# Sheet1_MEZ.net
KiCad netlist of a schematic drawn in Altium Designer
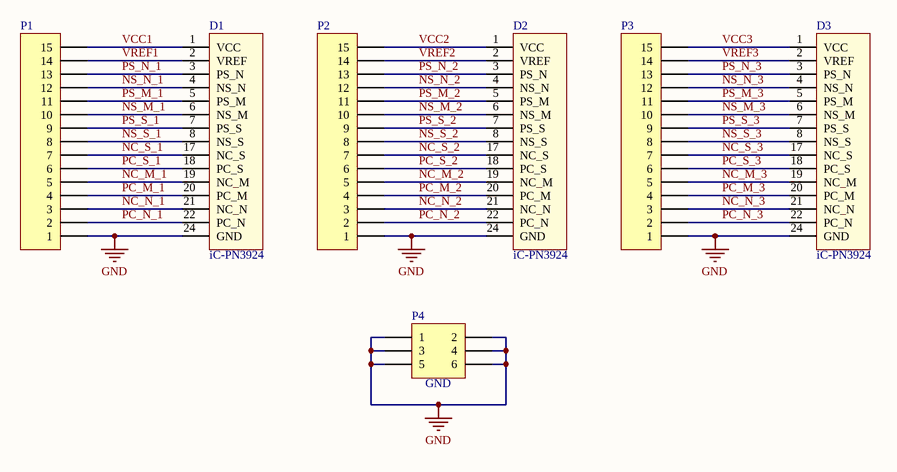
[diagram p0: Sheet1_MEZ.SchDoc]

(export (version "E")
  (design (tool "Eeschema 10.0.6"))
  (components
    (comp (ref "D1")
      (value "iC-PN3924")
      (footprint "iC-PN3924")
      (libsource (lib "Schlib") (part "iC-PN3924"))
    )
    (comp (ref "D2")
      (value "iC-PN3924")
      (footprint "iC-PN3924")
      (libsource (lib "Schlib") (part "iC-PN3924"))
    )
    (comp (ref "D3")
      (value "iC-PN3924")
      (footprint "iC-PN3924")
      (libsource (lib "Schlib") (part "iC-PN3924"))
    )
    (comp (ref "P1")
      (value "Header 15")
      (footprint "HDR1X15")
      (description "Header, 15-Pin")
      (fields (field (name "PUBLISHER") "Altium Limited"))
      (libsource (lib "Miscellaneous Connectors") (part "Header 15"))
    )
    (comp (ref "P2")
      (value "Header 15")
      (footprint "HDR1X15")
      (description "Header, 15-Pin")
      (fields (field (name "PUBLISHER") "Altium Limited"))
      (libsource (lib "Miscellaneous Connectors") (part "Header 15"))
    )
    (comp (ref "P3")
      (value "Header 15")
      (footprint "HDR1X15")
      (description "Header, 15-Pin")
      (fields (field (name "PUBLISHER") "Altium Limited"))
      (libsource (lib "Miscellaneous Connectors") (part "Header 15"))
    )
    (comp (ref "P4")
      (value "GND")
      (footprint "HDR2X3")
      (description "Header, 3-Pin, Dual row")
      (fields (field (name "PUBLISHER") "Altium Limited"))
      (libsource (lib "Miscellaneous Connectors") (part "Header 3X2"))
    )
  )
  (nets
    (net (code "1") (name "/NC_M_1") (class "Default")
      (node (ref "D1") (pin "19") (pinfunction "NC_M_19") (pintype "passive"))
      (node (ref "P1") (pin "5") (pinfunction "5_5") (pintype "passive"))
    )
    (net (code "2") (name "/NC_M_2") (class "Default")
      (node (ref "D2") (pin "19") (pinfunction "NC_M_19") (pintype "passive"))
      (node (ref "P2") (pin "5") (pinfunction "5_5") (pintype "passive"))
    )
    (net (code "3") (name "/NC_M_3") (class "Default")
      (node (ref "D3") (pin "19") (pinfunction "NC_M_19") (pintype "passive"))
      (node (ref "P3") (pin "5") (pinfunction "5_5") (pintype "passive"))
    )
    (net (code "4") (name "/NC_N_1") (class "Default")
      (node (ref "D1") (pin "21") (pinfunction "NC_N_21") (pintype "passive"))
      (node (ref "P1") (pin "3") (pinfunction "3_3") (pintype "passive"))
    )
    (net (code "5") (name "/NC_N_2") (class "Default")
      (node (ref "D2") (pin "21") (pinfunction "NC_N_21") (pintype "passive"))
      (node (ref "P2") (pin "3") (pinfunction "3_3") (pintype "passive"))
    )
    (net (code "6") (name "/NC_N_3") (class "Default")
      (node (ref "D3") (pin "21") (pinfunction "NC_N_21") (pintype "passive"))
      (node (ref "P3") (pin "3") (pinfunction "3_3") (pintype "passive"))
    )
    (net (code "7") (name "/NC_S_1") (class "Default")
      (node (ref "D1") (pin "17") (pinfunction "NC_S_17") (pintype "passive"))
      (node (ref "P1") (pin "7") (pinfunction "7_7") (pintype "passive"))
    )
    (net (code "8") (name "/NC_S_2") (class "Default")
      (node (ref "D2") (pin "17") (pinfunction "NC_S_17") (pintype "passive"))
      (node (ref "P2") (pin "7") (pinfunction "7_7") (pintype "passive"))
    )
    (net (code "9") (name "/NC_S_3") (class "Default")
      (node (ref "D3") (pin "17") (pinfunction "NC_S_17") (pintype "passive"))
      (node (ref "P3") (pin "7") (pinfunction "7_7") (pintype "passive"))
    )
    (net (code "10") (name "/NS_M_1") (class "Default")
      (node (ref "D1") (pin "6") (pinfunction "NS_M_6") (pintype "passive"))
      (node (ref "P1") (pin "10") (pinfunction "10_10") (pintype "passive"))
    )
    (net (code "11") (name "/NS_M_2") (class "Default")
      (node (ref "D2") (pin "6") (pinfunction "NS_M_6") (pintype "passive"))
      (node (ref "P2") (pin "10") (pinfunction "10_10") (pintype "passive"))
    )
    (net (code "12") (name "/NS_M_3") (class "Default")
      (node (ref "D3") (pin "6") (pinfunction "NS_M_6") (pintype "passive"))
      (node (ref "P3") (pin "10") (pinfunction "10_10") (pintype "passive"))
    )
    (net (code "13") (name "/NS_N_1") (class "Default")
      (node (ref "D1") (pin "4") (pinfunction "NS_N_4") (pintype "passive"))
      (node (ref "P1") (pin "12") (pinfunction "12_12") (pintype "passive"))
    )
    (net (code "14") (name "/NS_N_2") (class "Default")
      (node (ref "D2") (pin "4") (pinfunction "NS_N_4") (pintype "passive"))
      (node (ref "P2") (pin "12") (pinfunction "12_12") (pintype "passive"))
    )
    (net (code "15") (name "/NS_N_3") (class "Default")
      (node (ref "D3") (pin "4") (pinfunction "NS_N_4") (pintype "passive"))
      (node (ref "P3") (pin "12") (pinfunction "12_12") (pintype "passive"))
    )
    (net (code "16") (name "/NS_S_1") (class "Default")
      (node (ref "D1") (pin "8") (pinfunction "NS_S_8") (pintype "passive"))
      (node (ref "P1") (pin "8") (pinfunction "8_8") (pintype "passive"))
    )
    (net (code "17") (name "/NS_S_2") (class "Default")
      (node (ref "D2") (pin "8") (pinfunction "NS_S_8") (pintype "passive"))
      (node (ref "P2") (pin "8") (pinfunction "8_8") (pintype "passive"))
    )
    (net (code "18") (name "/NS_S_3") (class "Default")
      (node (ref "D3") (pin "8") (pinfunction "NS_S_8") (pintype "passive"))
      (node (ref "P3") (pin "8") (pinfunction "8_8") (pintype "passive"))
    )
    (net (code "19") (name "/PC_M_1") (class "Default")
      (node (ref "D1") (pin "20") (pinfunction "PC_M_20") (pintype "passive"))
      (node (ref "P1") (pin "4") (pinfunction "4_4") (pintype "passive"))
    )
    (net (code "20") (name "/PC_M_2") (class "Default")
      (node (ref "D2") (pin "20") (pinfunction "PC_M_20") (pintype "passive"))
      (node (ref "P2") (pin "4") (pinfunction "4_4") (pintype "passive"))
    )
    (net (code "21") (name "/PC_M_3") (class "Default")
      (node (ref "D3") (pin "20") (pinfunction "PC_M_20") (pintype "passive"))
      (node (ref "P3") (pin "4") (pinfunction "4_4") (pintype "passive"))
    )
    (net (code "22") (name "/PC_N_1") (class "Default")
      (node (ref "D1") (pin "22") (pinfunction "PC_N_22") (pintype "passive"))
      (node (ref "P1") (pin "2") (pinfunction "2_2") (pintype "passive"))
    )
    (net (code "23") (name "/PC_N_2") (class "Default")
      (node (ref "D2") (pin "22") (pinfunction "PC_N_22") (pintype "passive"))
      (node (ref "P2") (pin "2") (pinfunction "2_2") (pintype "passive"))
    )
    (net (code "24") (name "/PC_N_3") (class "Default")
      (node (ref "D3") (pin "22") (pinfunction "PC_N_22") (pintype "passive"))
      (node (ref "P3") (pin "2") (pinfunction "2_2") (pintype "passive"))
    )
    (net (code "25") (name "/PC_S_1") (class "Default")
      (node (ref "D1") (pin "18") (pinfunction "PC_S_18") (pintype "passive"))
      (node (ref "P1") (pin "6") (pinfunction "6_6") (pintype "passive"))
    )
    (net (code "26") (name "/PC_S_2") (class "Default")
      (node (ref "D2") (pin "18") (pinfunction "PC_S_18") (pintype "passive"))
      (node (ref "P2") (pin "6") (pinfunction "6_6") (pintype "passive"))
    )
    (net (code "27") (name "/PC_S_3") (class "Default")
      (node (ref "D3") (pin "18") (pinfunction "PC_S_18") (pintype "passive"))
      (node (ref "P3") (pin "6") (pinfunction "6_6") (pintype "passive"))
    )
    (net (code "28") (name "/PS_M_1") (class "Default")
      (node (ref "D1") (pin "5") (pinfunction "PS_M_5") (pintype "passive"))
      (node (ref "P1") (pin "11") (pinfunction "11_11") (pintype "passive"))
    )
    (net (code "29") (name "/PS_M_2") (class "Default")
      (node (ref "D2") (pin "5") (pinfunction "PS_M_5") (pintype "passive"))
      (node (ref "P2") (pin "11") (pinfunction "11_11") (pintype "passive"))
    )
    (net (code "30") (name "/PS_M_3") (class "Default")
      (node (ref "D3") (pin "5") (pinfunction "PS_M_5") (pintype "passive"))
      (node (ref "P3") (pin "11") (pinfunction "11_11") (pintype "passive"))
    )
    (net (code "31") (name "/PS_N_1") (class "Default")
      (node (ref "D1") (pin "3") (pinfunction "PS_N_3") (pintype "passive"))
      (node (ref "P1") (pin "13") (pinfunction "13_13") (pintype "passive"))
    )
    (net (code "32") (name "/PS_N_2") (class "Default")
      (node (ref "D2") (pin "3") (pinfunction "PS_N_3") (pintype "passive"))
      (node (ref "P2") (pin "13") (pinfunction "13_13") (pintype "passive"))
    )
    (net (code "33") (name "/PS_N_3") (class "Default")
      (node (ref "D3") (pin "3") (pinfunction "PS_N_3") (pintype "passive"))
      (node (ref "P3") (pin "13") (pinfunction "13_13") (pintype "passive"))
    )
    (net (code "34") (name "/PS_S_1") (class "Default")
      (node (ref "D1") (pin "7") (pinfunction "PS_S_7") (pintype "passive"))
      (node (ref "P1") (pin "9") (pinfunction "9_9") (pintype "passive"))
    )
    (net (code "35") (name "/PS_S_2") (class "Default")
      (node (ref "D2") (pin "7") (pinfunction "PS_S_7") (pintype "passive"))
      (node (ref "P2") (pin "9") (pinfunction "9_9") (pintype "passive"))
    )
    (net (code "36") (name "/PS_S_3") (class "Default")
      (node (ref "D3") (pin "7") (pinfunction "PS_S_7") (pintype "passive"))
      (node (ref "P3") (pin "9") (pinfunction "9_9") (pintype "passive"))
    )
    (net (code "37") (name "/VCC1") (class "Default")
      (node (ref "D1") (pin "1") (pinfunction "VCC_1") (pintype "passive"))
      (node (ref "P1") (pin "15") (pinfunction "15_15") (pintype "passive"))
    )
    (net (code "38") (name "/VCC2") (class "Default")
      (node (ref "D2") (pin "1") (pinfunction "VCC_1") (pintype "passive"))
      (node (ref "P2") (pin "15") (pinfunction "15_15") (pintype "passive"))
    )
    (net (code "39") (name "/VCC3") (class "Default")
      (node (ref "D3") (pin "1") (pinfunction "VCC_1") (pintype "passive"))
      (node (ref "P3") (pin "15") (pinfunction "15_15") (pintype "passive"))
    )
    (net (code "40") (name "/VREF1") (class "Default")
      (node (ref "D1") (pin "2") (pinfunction "VREF_2") (pintype "passive"))
      (node (ref "P1") (pin "14") (pinfunction "14_14") (pintype "passive"))
    )
    (net (code "41") (name "/VREF2") (class "Default")
      (node (ref "D2") (pin "2") (pinfunction "VREF_2") (pintype "passive"))
      (node (ref "P2") (pin "14") (pinfunction "14_14") (pintype "passive"))
    )
    (net (code "42") (name "/VREF3") (class "Default")
      (node (ref "D3") (pin "2") (pinfunction "VREF_2") (pintype "passive"))
      (node (ref "P3") (pin "14") (pinfunction "14_14") (pintype "passive"))
    )
    (net (code "43") (name "GND") (class "Default")
      (node (ref "D1") (pin "24") (pinfunction "GND_24") (pintype "passive"))
      (node (ref "D2") (pin "24") (pinfunction "GND_24") (pintype "passive"))
      (node (ref "D3") (pin "24") (pinfunction "GND_24") (pintype "passive"))
      (node (ref "P1") (pin "1") (pinfunction "1_1") (pintype "passive"))
      (node (ref "P2") (pin "1") (pinfunction "1_1") (pintype "passive"))
      (node (ref "P3") (pin "1") (pinfunction "1_1") (pintype "passive"))
      (node (ref "P4") (pin "1") (pinfunction "1_1") (pintype "passive"))
      (node (ref "P4") (pin "2") (pinfunction "2_2") (pintype "passive"))
      (node (ref "P4") (pin "3") (pinfunction "3_3") (pintype "passive"))
      (node (ref "P4") (pin "4") (pinfunction "4_4") (pintype "passive"))
      (node (ref "P4") (pin "5") (pinfunction "5_5") (pintype "passive"))
      (node (ref "P4") (pin "6") (pinfunction "6_6") (pintype "passive"))
    )
  )
)
